# Connectors.net
KiCad netlist of a schematic drawn in Altium Designer
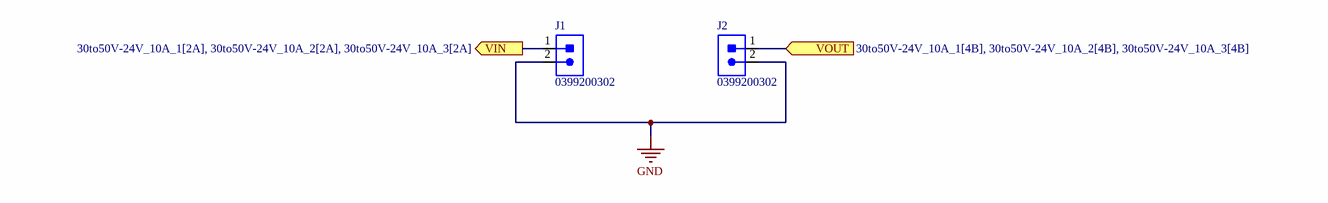
[diagram p0: Connectors.SchDoc]

(export (version "E")
  (design (tool "Eeschema 10.0.6"))
  (components
    (comp (ref "J1")
      (value "CONN_SCREW_TERM_115A")
      (footprint "MOLEX-0399200302")
      (description "CONN TERM BLOCK 2POS 15MM 1-8AWG")
      (fields (field (name "MANUFACTURER PART NUMBER 1") "0399200302"))
      (libsource (lib "") (part "CONN_SCREW_TERM_115A_1"))
    )
    (comp (ref "J2")
      (value "CONN_SCREW_TERM_115A")
      (footprint "MOLEX-0399200302")
      (description "CONN TERM BLOCK 2POS 15MM 1-8AWG")
      (fields (field (name "MANUFACTURER PART NUMBER 1") "0399200302"))
      (libsource (lib "UWRT_Schematic_Library_2020") (part "CONN_SCREW_TERM_115A"))
    )
  )
  (nets
    (net (code "1") (name "/VIN") (class "Default")
      (node (ref "J1") (pin "1") (pinfunction "1_1") (pintype "passive"))
    )
    (net (code "2") (name "/VOUT") (class "Default")
      (node (ref "J2") (pin "1") (pinfunction "1_1") (pintype "passive"))
    )
    (net (code "3") (name "GND") (class "Default")
      (node (ref "J1") (pin "2") (pinfunction "2_2") (pintype "passive"))
      (node (ref "J2") (pin "2") (pinfunction "2_2") (pintype "passive"))
    )
  )
)
